# Connectors.net
KiCad netlist of a schematic drawn in Altium Designer
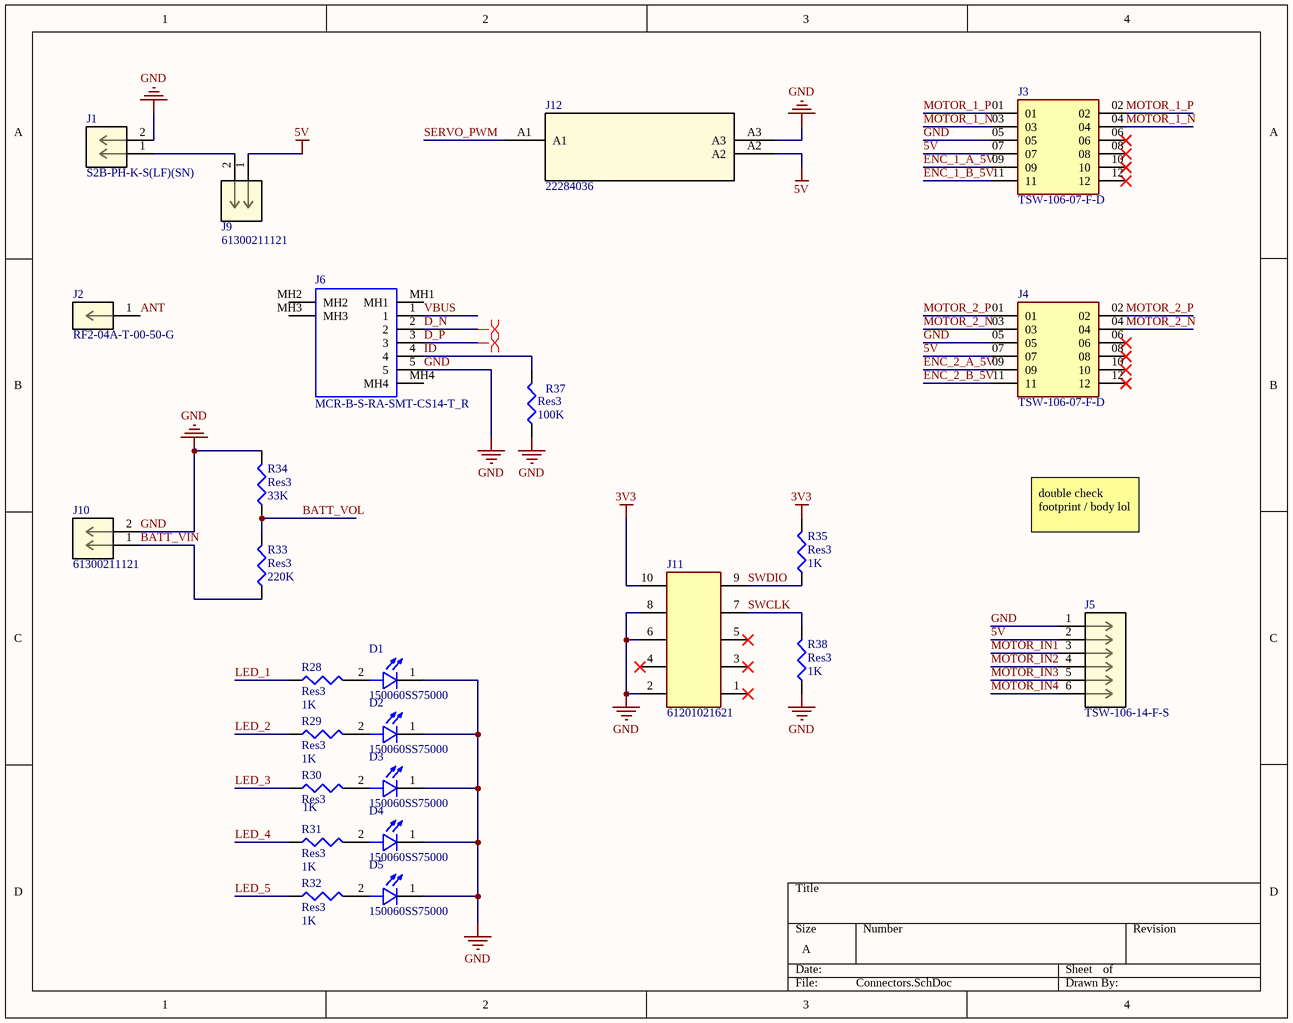
[diagram p0: Connectors.SchDoc]

(export (version "E")
  (design (tool "Eeschema 10.0.6"))
  (components
    (comp (ref "D1")
      (value "150060SS75000")
      (footprint "swarm_crawler_pcb:LED_150060SS75000")
      (description "Standard LEDs - SMD WL-SMCW SMDMono TpVw Waterclr 0603 SprRed")
      (fields (field (name "MF") "WÃ¼rth Elektronik"))
      (libsource (lib "swarm_crawler_sch") (part "150060SS75000"))
    )
    (comp (ref "D2")
      (value "150060SS75000")
      (footprint "swarm_crawler_pcb:LED_150060SS75000")
      (description "Standard LEDs - SMD WL-SMCW SMDMono TpVw Waterclr 0603 SprRed")
      (fields (field (name "MF") "WÃ¼rth Elektronik"))
      (libsource (lib "swarm_crawler_sch") (part "150060SS75000"))
    )
    (comp (ref "D3")
      (value "150060SS75000")
      (footprint "swarm_crawler_pcb:LED_150060SS75000")
      (description "Standard LEDs - SMD WL-SMCW SMDMono TpVw Waterclr 0603 SprRed")
      (fields (field (name "MF") "WÃ¼rth Elektronik"))
      (libsource (lib "swarm_crawler_sch") (part "150060SS75000"))
    )
    (comp (ref "D4")
      (value "150060SS75000")
      (footprint "swarm_crawler_pcb:LED_150060SS75000")
      (description "Standard LEDs - SMD WL-SMCW SMDMono TpVw Waterclr 0603 SprRed")
      (fields (field (name "MF") "WÃ¼rth Elektronik"))
      (libsource (lib "swarm_crawler_sch") (part "150060SS75000"))
    )
    (comp (ref "D5")
      (value "150060SS75000")
      (footprint "swarm_crawler_pcb:LED_150060SS75000")
      (description "Standard LEDs - SMD WL-SMCW SMDMono TpVw Waterclr 0603 SprRed")
      (fields (field (name "MF") "WÃ¼rth Elektronik"))
      (libsource (lib "swarm_crawler_sch") (part "150060SS75000"))
    )
    (comp (ref "J1")
      (value "S2B-PH-K-S(LF)(SN)")
      (footprint "swarm_crawler_pcb:CONN_S2B-PH-K-S_JST")
      (description "No Description Available")
      (fields (field (name "COPYRIGHT") "Copyright (C) 2023 Ultra Librarian. All rights reserved."))
      (libsource (lib "swarm_crawler_sch") (part "S2B-PH-K-S(LF)(SN)"))
    )
    (comp (ref "J2")
      (value "RF2-04A-T-00-50-G")
      (footprint "swarm_crawler_pcb:CONN_RF2-04A-T-00-50-G_ADM")
      (description "No Description Available")
      (fields (field (name "COPYRIGHT") "Copyright (C) 2023 Ultra Librarian. All rights reserved."))
      (libsource (lib "swarm_crawler_sch") (part "RF2-04A-T-00-50-G"))
    )
    (comp (ref "J3")
      (value "TSW-106-07-F-D")
      (footprint "swarm_crawler_pcb:SAMTEC_TSW-106-07-F-D")
      (fields (field (name "MF") "Samtec"))
      (libsource (lib "swarm_crawler_sch") (part "TSW-106-07-F-D"))
    )
    (comp (ref "J4")
      (value "TSW-106-07-F-D")
      (footprint "swarm_crawler_pcb:SAMTEC_TSW-106-07-F-D")
      (fields (field (name "MF") "Samtec"))
      (libsource (lib "swarm_crawler_sch") (part "TSW-106-07-F-D"))
    )
    (comp (ref "J5")
      (value "TSW-106-14-F-S")
      (footprint "swarm_crawler_pcb:CON6_1X6_TU_TSW")
      (description "No Description Available")
      (fields (field (name "COPYRIGHT") "Copyright (C) 2023 Ultra Librarian. All rights reserved."))
      (libsource (lib "swarm_crawler_sch") (part "TSW-106-14-F-S"))
    )
    (comp (ref "J6")
      (value "MCR-B-S-RA-SMT-CS14-T_R")
      (footprint "swarm_crawler_pcb:MCRBSRASMTCS14TR")
      (description "USB - micro B Receptacle Connector 5 Position Surface Mount, Right Angle")
      (fields (field (name "MANUFACTURER_PART_NUMBER") "MCR-B-S-RA-SMT-CS14-T/R"))
      (libsource (lib "swarm_crawler_sch") (part "MCR-B-S-RA-SMT-CS14-T_R"))
    )
    (comp (ref "J9")
      (value "61300211121")
      (footprint "swarm_crawler_pcb:CONN_61300211121_WRE")
      (description "No Description Available")
      (fields (field (name "COPYRIGHT") "Copyright (C) 2023 Ultra Librarian. All rights reserved."))
      (libsource (lib "swarm_crawler_sch") (part "61300211121"))
    )
    (comp (ref "J10")
      (value "61300211121")
      (footprint "swarm_crawler_pcb:CONN_61300211121_WRE")
      (description "No Description Available")
      (fields (field (name "COPYRIGHT") "Copyright (C) 2023 Ultra Librarian. All rights reserved."))
      (libsource (lib "") (part "61300211121_1"))
    )
    (comp (ref "J11")
      (value "61201021621")
      (footprint "swarm_crawler_pcb:61201021621")
      (description "Connector Header Through Hole 10 position 0.100 _2.54mm_")
      (fields (field (name "MF") "Wurth Electronics"))
      (libsource (lib "swarm_crawler_sch") (part "61201021621"))
    )
    (comp (ref "J12")
      (value "22284036")
      (footprint "swarm_crawler_pcb:22-28-4036_MOL")
      (description "No Description Available")
      (fields (field (name "COPYRIGHT") "Copyright (C) 2023 Ultra Librarian. All rights reserved."))
      (libsource (lib "swarm_crawler_sch") (part "22284036"))
    )
    (comp (ref "R28")
      (value "Res3")
      (footprint "J1-0603")
      (description "Resistor")
      (fields (field (name "ALTIUM_VALUE") "1K") (field (name "PUBLISHER") "Altium Limited"))
      (libsource (lib "Miscellaneous Devices") (part "Res3"))
    )
    (comp (ref "R29")
      (value "Res3")
      (footprint "J1-0603")
      (description "Resistor")
      (fields (field (name "ALTIUM_VALUE") "1K") (field (name "PUBLISHER") "Altium Limited"))
      (libsource (lib "Miscellaneous Devices") (part "Res3"))
    )
    (comp (ref "R30")
      (value "Res3")
      (footprint "J1-0603")
      (description "Resistor")
      (fields (field (name "ALTIUM_VALUE") "1K") (field (name "PUBLISHER") "Altium Limited"))
      (libsource (lib "Miscellaneous Devices") (part "Res3"))
    )
    (comp (ref "R31")
      (value "Res3")
      (footprint "J1-0603")
      (description "Resistor")
      (fields (field (name "ALTIUM_VALUE") "1K") (field (name "PUBLISHER") "Altium Limited"))
      (libsource (lib "Miscellaneous Devices") (part "Res3"))
    )
    (comp (ref "R32")
      (value "Res3")
      (footprint "J1-0603")
      (description "Resistor")
      (fields (field (name "ALTIUM_VALUE") "1K") (field (name "PUBLISHER") "Altium Limited"))
      (libsource (lib "Miscellaneous Devices") (part "Res3"))
    )
    (comp (ref "R33")
      (value "Res3")
      (footprint "J1-0603")
      (description "Resistor")
      (fields (field (name "ALTIUM_VALUE") "220K") (field (name "PUBLISHER") "Altium Limited"))
      (libsource (lib "Miscellaneous Devices") (part "Res3"))
    )
    (comp (ref "R34")
      (value "Res3")
      (footprint "J1-0603")
      (description "Resistor")
      (fields (field (name "ALTIUM_VALUE") "33K") (field (name "PUBLISHER") "Altium Limited"))
      (libsource (lib "Miscellaneous Devices") (part "Res3"))
    )
    (comp (ref "R35")
      (value "Res3")
      (footprint "J1-0603")
      (description "Resistor")
      (fields (field (name "ALTIUM_VALUE") "1K") (field (name "PUBLISHER") "Altium Limited"))
      (libsource (lib "Miscellaneous Devices") (part "Res3"))
    )
    (comp (ref "R37")
      (value "Res3")
      (footprint "J1-0603")
      (description "Resistor")
      (fields (field (name "ALTIUM_VALUE") "100K") (field (name "PUBLISHER") "Altium Limited"))
      (libsource (lib "Miscellaneous Devices") (part "Res3"))
    )
    (comp (ref "R38")
      (value "Res3")
      (footprint "J1-0603")
      (description "Resistor")
      (fields (field (name "ALTIUM_VALUE") "1K") (field (name "PUBLISHER") "Altium Limited"))
      (libsource (lib "Miscellaneous Devices") (part "Res3"))
    )
  )
  (nets
    (net (code "1") (name "/ANT") (class "Default")
      (node (ref "J2") (pin "1") (pinfunction "1_1") (pintype "passive"))
    )
    (net (code "2") (name "/BATT_VIN") (class "Default")
      (node (ref "J10") (pin "1") (pinfunction "1_1") (pintype "passive"))
      (node (ref "R33") (pin "1") (pinfunction "1_1") (pintype "passive"))
    )
    (net (code "3") (name "/BATT_VOL") (class "Default")
      (node (ref "R33") (pin "2") (pinfunction "2_2") (pintype "passive"))
      (node (ref "R34") (pin "1") (pinfunction "1_1") (pintype "passive"))
    )
    (net (code "4") (name "/D_N") (class "Default")
      (node (ref "J6") (pin "2") (pinfunction "2_2") (pintype "passive"))
    )
    (net (code "5") (name "/D_P") (class "Default")
      (node (ref "J6") (pin "3") (pinfunction "3_3") (pintype "passive"))
    )
    (net (code "6") (name "/ENC_1_A_5V") (class "Default")
      (node (ref "J3") (pin "09") (pinfunction "09_09") (pintype "passive"))
    )
    (net (code "7") (name "/ENC_1_B_5V") (class "Default")
      (node (ref "J3") (pin "11") (pinfunction "11_11") (pintype "passive"))
    )
    (net (code "8") (name "/ENC_2_A_5V") (class "Default")
      (node (ref "J4") (pin "09") (pinfunction "09_09") (pintype "passive"))
    )
    (net (code "9") (name "/ENC_2_B_5V") (class "Default")
      (node (ref "J4") (pin "11") (pinfunction "11_11") (pintype "passive"))
    )
    (net (code "10") (name "/ID") (class "Default")
      (node (ref "J6") (pin "4") (pinfunction "4_4") (pintype "passive"))
      (node (ref "R37") (pin "2") (pinfunction "2_2") (pintype "passive"))
    )
    (net (code "11") (name "/LED_1") (class "Default")
      (node (ref "R28") (pin "1") (pinfunction "1_1") (pintype "passive"))
    )
    (net (code "12") (name "/LED_2") (class "Default")
      (node (ref "R29") (pin "1") (pinfunction "1_1") (pintype "passive"))
    )
    (net (code "13") (name "/LED_3") (class "Default")
      (node (ref "R30") (pin "1") (pinfunction "1_1") (pintype "passive"))
    )
    (net (code "14") (name "/LED_4") (class "Default")
      (node (ref "R31") (pin "1") (pinfunction "1_1") (pintype "passive"))
    )
    (net (code "15") (name "/LED_5") (class "Default")
      (node (ref "R32") (pin "1") (pinfunction "1_1") (pintype "passive"))
    )
    (net (code "16") (name "/MOTOR_1_N") (class "Default")
      (node (ref "J3") (pin "03") (pinfunction "03_03") (pintype "passive"))
      (node (ref "J3") (pin "04") (pinfunction "04_04") (pintype "passive"))
    )
    (net (code "17") (name "/MOTOR_1_P") (class "Default")
      (node (ref "J3") (pin "01") (pinfunction "01_01") (pintype "passive"))
      (node (ref "J3") (pin "02") (pinfunction "02_02") (pintype "passive"))
    )
    (net (code "18") (name "/MOTOR_2_N") (class "Default")
      (node (ref "J4") (pin "03") (pinfunction "03_03") (pintype "passive"))
      (node (ref "J4") (pin "04") (pinfunction "04_04") (pintype "passive"))
    )
    (net (code "19") (name "/MOTOR_2_P") (class "Default")
      (node (ref "J4") (pin "01") (pinfunction "01_01") (pintype "passive"))
      (node (ref "J4") (pin "02") (pinfunction "02_02") (pintype "passive"))
    )
    (net (code "20") (name "/MOTOR_IN1") (class "Default")
      (node (ref "J5") (pin "3") (pinfunction "3_3") (pintype "passive"))
    )
    (net (code "21") (name "/MOTOR_IN2") (class "Default")
      (node (ref "J5") (pin "4") (pinfunction "4_4") (pintype "passive"))
    )
    (net (code "22") (name "/MOTOR_IN3") (class "Default")
      (node (ref "J5") (pin "5") (pinfunction "5_5") (pintype "passive"))
    )
    (net (code "23") (name "/MOTOR_IN4") (class "Default")
      (node (ref "J5") (pin "6") (pinfunction "6_6") (pintype "passive"))
    )
    (net (code "24") (name "/SERVO_PWM") (class "Default")
      (node (ref "J12") (pin "A1") (pinfunction "A1_A1") (pintype "passive"))
    )
    (net (code "25") (name "/SWCLK") (class "Default")
      (node (ref "J11") (pin "7") (pinfunction "7_7") (pintype "passive"))
      (node (ref "R38") (pin "2") (pinfunction "2_2") (pintype "passive"))
    )
    (net (code "26") (name "/SWDIO") (class "Default")
      (node (ref "J11") (pin "9") (pinfunction "9_9") (pintype "passive"))
      (node (ref "R35") (pin "1") (pinfunction "1_1") (pintype "passive"))
    )
    (net (code "27") (name "/VBUS") (class "Default")
      (node (ref "J6") (pin "1") (pinfunction "1_1") (pintype "passive"))
    )
    (net (code "28") (name "3V3") (class "Default")
      (node (ref "J11") (pin "10") (pinfunction "10_10") (pintype "passive"))
      (node (ref "R35") (pin "2") (pinfunction "2_2") (pintype "passive"))
    )
    (net (code "29") (name "5V") (class "Default")
      (node (ref "J12") (pin "A2") (pinfunction "A2_A2") (pintype "passive"))
      (node (ref "J3") (pin "07") (pinfunction "07_07") (pintype "passive"))
      (node (ref "J4") (pin "07") (pinfunction "07_07") (pintype "passive"))
      (node (ref "J5") (pin "2") (pinfunction "2_2") (pintype "passive"))
      (node (ref "J9") (pin "1") (pinfunction "1_1") (pintype "passive"))
    )
    (net (code "30") (name "GND") (class "Default")
      (node (ref "D1") (pin "1") (pinfunction "C_1") (pintype "passive"))
      (node (ref "D2") (pin "1") (pinfunction "C_1") (pintype "passive"))
      (node (ref "D3") (pin "1") (pinfunction "C_1") (pintype "passive"))
      (node (ref "D4") (pin "1") (pinfunction "C_1") (pintype "passive"))
      (node (ref "D5") (pin "1") (pinfunction "C_1") (pintype "passive"))
      (node (ref "J1") (pin "2") (pinfunction "2_2") (pintype "passive"))
      (node (ref "J10") (pin "2") (pinfunction "2_2") (pintype "passive"))
      (node (ref "J11") (pin "2") (pinfunction "2_2") (pintype "passive"))
      (node (ref "J11") (pin "6") (pinfunction "6_6") (pintype "passive"))
      (node (ref "J11") (pin "8") (pinfunction "8_8") (pintype "passive"))
      (node (ref "J12") (pin "A3") (pinfunction "A3_A3") (pintype "passive"))
      (node (ref "J3") (pin "05") (pinfunction "05_05") (pintype "passive"))
      (node (ref "J4") (pin "05") (pinfunction "05_05") (pintype "passive"))
      (node (ref "J5") (pin "1") (pinfunction "1_1") (pintype "passive"))
      (node (ref "J6") (pin "5") (pinfunction "5_5") (pintype "passive"))
      (node (ref "R34") (pin "2") (pinfunction "2_2") (pintype "passive"))
      (node (ref "R37") (pin "1") (pinfunction "1_1") (pintype "passive"))
      (node (ref "R38") (pin "1") (pinfunction "1_1") (pintype "passive"))
    )
    (net (code "31") (name "Net-(D1-A)") (class "Default")
      (node (ref "D1") (pin "2") (pinfunction "A_2") (pintype "passive"))
      (node (ref "R28") (pin "2") (pinfunction "2_2") (pintype "passive"))
    )
    (net (code "32") (name "Net-(D2-A)") (class "Default")
      (node (ref "D2") (pin "2") (pinfunction "A_2") (pintype "passive"))
      (node (ref "R29") (pin "2") (pinfunction "2_2") (pintype "passive"))
    )
    (net (code "33") (name "Net-(D3-A)") (class "Default")
      (node (ref "D3") (pin "2") (pinfunction "A_2") (pintype "passive"))
      (node (ref "R30") (pin "2") (pinfunction "2_2") (pintype "passive"))
    )
    (net (code "34") (name "Net-(D4-A)") (class "Default")
      (node (ref "D4") (pin "2") (pinfunction "A_2") (pintype "passive"))
      (node (ref "R31") (pin "2") (pinfunction "2_2") (pintype "passive"))
    )
    (net (code "35") (name "Net-(D5-A)") (class "Default")
      (node (ref "D5") (pin "2") (pinfunction "A_2") (pintype "passive"))
      (node (ref "R32") (pin "2") (pinfunction "2_2") (pintype "passive"))
    )
    (net (code "36") (name "Net-(J1-Pad1)") (class "Default")
      (node (ref "J1") (pin "1") (pinfunction "1_1") (pintype "passive"))
      (node (ref "J9") (pin "2") (pinfunction "2_2") (pintype "passive"))
    )
    (net (code "37") (name "unconnected-(J3-Pad06)") (class "Default")
      (node (ref "J3") (pin "06") (pinfunction "06_06") (pintype "passive+no_connect"))
    )
    (net (code "38") (name "unconnected-(J3-Pad08)") (class "Default")
      (node (ref "J3") (pin "08") (pinfunction "08_08") (pintype "passive+no_connect"))
    )
    (net (code "39") (name "unconnected-(J3-Pad10)") (class "Default")
      (node (ref "J3") (pin "10") (pinfunction "10_10") (pintype "passive+no_connect"))
    )
    (net (code "40") (name "unconnected-(J3-Pad12)") (class "Default")
      (node (ref "J3") (pin "12") (pinfunction "12_12") (pintype "passive+no_connect"))
    )
    (net (code "41") (name "unconnected-(J4-Pad06)") (class "Default")
      (node (ref "J4") (pin "06") (pinfunction "06_06") (pintype "passive+no_connect"))
    )
    (net (code "42") (name "unconnected-(J4-Pad08)") (class "Default")
      (node (ref "J4") (pin "08") (pinfunction "08_08") (pintype "passive+no_connect"))
    )
    (net (code "43") (name "unconnected-(J4-Pad10)") (class "Default")
      (node (ref "J4") (pin "10") (pinfunction "10_10") (pintype "passive+no_connect"))
    )
    (net (code "44") (name "unconnected-(J4-Pad12)") (class "Default")
      (node (ref "J4") (pin "12") (pinfunction "12_12") (pintype "passive+no_connect"))
    )
    (net (code "45") (name "unconnected-(J6-PadMH1)") (class "Default")
      (node (ref "J6") (pin "MH1") (pinfunction "MH1_MH1") (pintype "passive"))
    )
    (net (code "46") (name "unconnected-(J6-PadMH2)") (class "Default")
      (node (ref "J6") (pin "MH2") (pinfunction "MH2_MH2") (pintype "passive"))
    )
    (net (code "47") (name "unconnected-(J6-PadMH3)") (class "Default")
      (node (ref "J6") (pin "MH3") (pinfunction "MH3_MH3") (pintype "passive"))
    )
    (net (code "48") (name "unconnected-(J6-PadMH4)") (class "Default")
      (node (ref "J6") (pin "MH4") (pinfunction "MH4_MH4") (pintype "passive"))
    )
    (net (code "49") (name "unconnected-(J11-Pad1)") (class "Default")
      (node (ref "J11") (pin "1") (pinfunction "1_1") (pintype "passive+no_connect"))
    )
    (net (code "50") (name "unconnected-(J11-Pad3)") (class "Default")
      (node (ref "J11") (pin "3") (pinfunction "3_3") (pintype "passive+no_connect"))
    )
    (net (code "51") (name "unconnected-(J11-Pad4)") (class "Default")
      (node (ref "J11") (pin "4") (pinfunction "4_4") (pintype "passive+no_connect"))
    )
    (net (code "52") (name "unconnected-(J11-Pad5)") (class "Default")
      (node (ref "J11") (pin "5") (pinfunction "5_5") (pintype "passive+no_connect"))
    )
  )
)
